# 10.net
KiCad netlist of a schematic drawn in Altium Designer
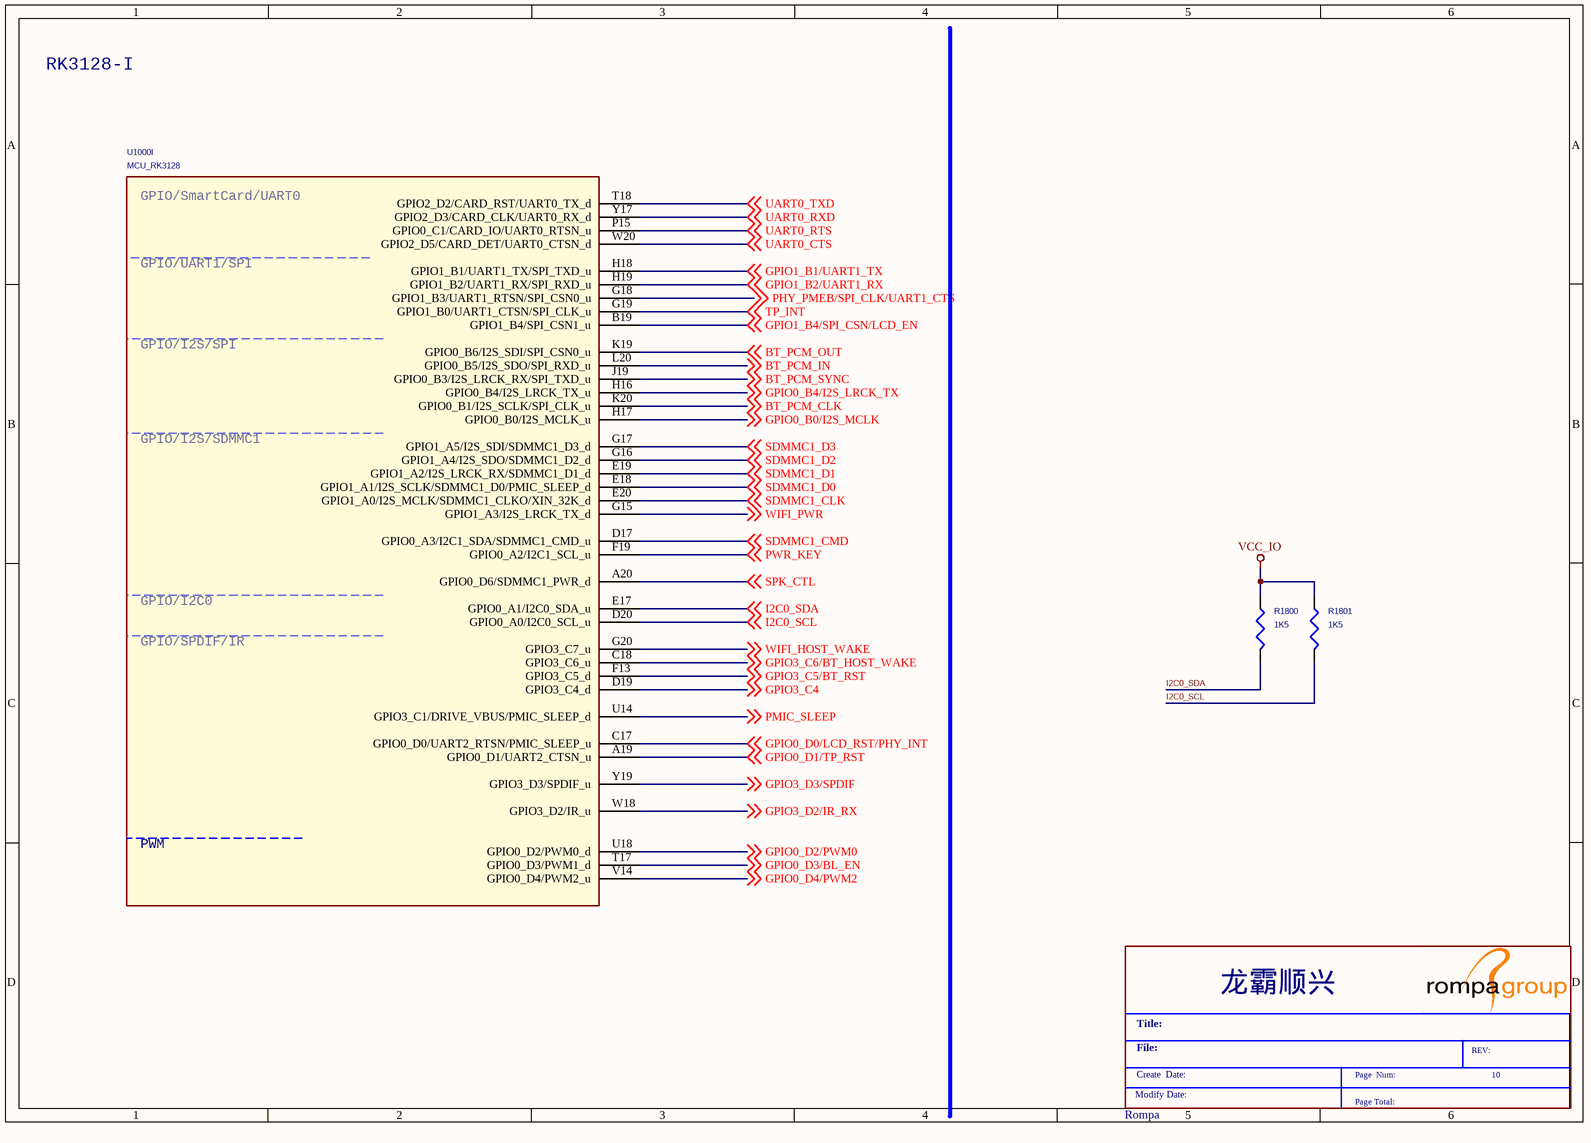
[diagram p0: 10.SchDoc]

(export (version "E")
  (design (tool "Eeschema 10.0.6"))
  (components
    (comp (ref "*")
      (value "Rompa")
      (fields (field (name "SCHEMATIC PAGE NUMBER") "10"))
      (libsource (lib "RK3128_BETA_V03_20151231_Library") (part "Rompa"))
    )
    (comp (ref "R1800")
      (value "1K5")
      (footprint "R0402")
      (description "ROHS CHIP RES 4.7K 1/16W 5%")
      (libsource (lib "*") (part "RES 1B"))
    )
    (comp (ref "R1801")
      (value "1K5")
      (footprint "R0402")
      (description "ROHS CHIP RES 4.7K 1/16W 5%")
      (libsource (lib "*") (part "RES 1B"))
    )
    (comp (ref "U1000")
      (value "MCU_RK3128")
      (footprint "BGA316-14X14-0.65")
      (libsource (lib "*") (part "MCU_RK3128"))
    )
  )
  (nets
    (net (code "1") (name "BT_PCM_CLK") (class "Default")
      (node (ref "U1000") (pin "K20") (pinfunction "GPIO0_B1/I2S_SCLK/SPI_CLK_u_K20") (pintype "passive"))
    )
    (net (code "2") (name "BT_PCM_IN") (class "Default")
      (node (ref "U1000") (pin "L20") (pinfunction "GPIO0_B5/I2S_SDO/SPI_RXD_u_L20") (pintype "passive"))
    )
    (net (code "3") (name "BT_PCM_OUT") (class "Default")
      (node (ref "U1000") (pin "K19") (pinfunction "GPIO0_B6/I2S_SDI/SPI_CSN0_u_K19") (pintype "passive"))
    )
    (net (code "4") (name "BT_PCM_SYNC") (class "Default")
      (node (ref "U1000") (pin "J19") (pinfunction "GPIO0_B3/I2S_LRCK_RX/SPI_TXD_u_J19") (pintype "passive"))
    )
    (net (code "5") (name "GPIO0_B0{slash}I2S_MCLK") (class "Default")
      (node (ref "U1000") (pin "H17") (pinfunction "GPIO0_B0/I2S_MCLK_u_H17") (pintype "passive"))
    )
    (net (code "6") (name "GPIO0_B4{slash}I2S_LRCK_TX") (class "Default")
      (node (ref "U1000") (pin "H16") (pinfunction "GPIO0_B4/I2S_LRCK_TX_u_H16") (pintype "passive"))
    )
    (net (code "7") (name "GPIO0_D0{slash}LCD_RST{slash}PHY_INT") (class "Default")
      (node (ref "U1000") (pin "C17") (pinfunction "GPIO0_D0/UART2_RTSN/PMIC_SLEEP_u_C17") (pintype "passive"))
    )
    (net (code "8") (name "GPIO0_D1{slash}TP_RST") (class "Default")
      (node (ref "U1000") (pin "A19") (pinfunction "GPIO0_D1/UART2_CTSN_u_A19") (pintype "passive"))
    )
    (net (code "9") (name "GPIO0_D2{slash}PWM0") (class "Default")
      (node (ref "U1000") (pin "U18") (pinfunction "GPIO0_D2/PWM0_d_U18") (pintype "passive"))
    )
    (net (code "10") (name "GPIO0_D3{slash}BL_EN") (class "Default")
      (node (ref "U1000") (pin "T17") (pinfunction "GPIO0_D3/PWM1_d_T17") (pintype "passive"))
    )
    (net (code "11") (name "GPIO0_D4{slash}PWM2") (class "Default")
      (node (ref "U1000") (pin "V14") (pinfunction "GPIO0_D4/PWM2_u_V14") (pintype "passive"))
    )
    (net (code "12") (name "GPIO1_B1{slash}UART1_TX") (class "Default")
      (node (ref "U1000") (pin "H18") (pinfunction "GPIO1_B1/UART1_TX/SPI_TXD_u_H18") (pintype "passive"))
    )
    (net (code "13") (name "GPIO1_B2{slash}UART1_RX") (class "Default")
      (node (ref "U1000") (pin "H19") (pinfunction "GPIO1_B2/UART1_RX/SPI_RXD_u_H19") (pintype "passive"))
    )
    (net (code "14") (name "GPIO1_B4{slash}SPI_CSN{slash}LCD_EN") (class "Default")
      (node (ref "U1000") (pin "B19") (pinfunction "GPIO1_B4/SPI_CSN1_u_B19") (pintype "passive"))
    )
    (net (code "15") (name "GPIO3_C4") (class "Default")
      (node (ref "U1000") (pin "D19") (pinfunction "GPIO3_C4_d_D19") (pintype "passive"))
    )
    (net (code "16") (name "GPIO3_C5{slash}BT_RST") (class "Default")
      (node (ref "U1000") (pin "F13") (pinfunction "GPIO3_C5_d_F13") (pintype "passive"))
    )
    (net (code "17") (name "GPIO3_C6{slash}BT_HOST_WAKE") (class "Default")
      (node (ref "U1000") (pin "C18") (pinfunction "GPIO3_C6_u_C18") (pintype "passive"))
    )
    (net (code "18") (name "GPIO3_D2{slash}IR_RX") (class "Default")
      (node (ref "U1000") (pin "W18") (pinfunction "GPIO3_D2/IR_u_W18") (pintype "passive"))
    )
    (net (code "19") (name "GPIO3_D3{slash}SPDIF") (class "Default")
      (node (ref "U1000") (pin "Y19") (pinfunction "GPIO3_D3/SPDIF_u_Y19") (pintype "passive"))
    )
    (net (code "20") (name "I2C0_SCL") (class "Default")
      (node (ref "R1801") (pin "2") (pinfunction "2_2") (pintype "passive"))
      (node (ref "U1000") (pin "D20") (pinfunction "GPIO0_A0/I2C0_SCL_u_D20") (pintype "passive"))
    )
    (net (code "21") (name "I2C0_SDA") (class "Default")
      (node (ref "R1800") (pin "2") (pinfunction "2_2") (pintype "passive"))
      (node (ref "U1000") (pin "E17") (pinfunction "GPIO0_A1/I2C0_SDA_u_E17") (pintype "passive"))
    )
    (net (code "22") (name "PHY_PMEB{slash}SPI_CLK{slash}UART1_CTS") (class "Default")
      (node (ref "U1000") (pin "G18") (pinfunction "GPIO1_B3/UART1_RTSN/SPI_CSN0_u_G18") (pintype "passive"))
    )
    (net (code "23") (name "PMIC_SLEEP") (class "Default")
      (node (ref "U1000") (pin "U14") (pinfunction "GPIO3_C1/DRIVE_VBUS/PMIC_SLEEP_d_U14") (pintype "passive"))
    )
    (net (code "24") (name "PWR_KEY") (class "Default")
      (node (ref "U1000") (pin "F19") (pinfunction "GPIO0_A2/I2C1_SCL_u_F19") (pintype "passive"))
    )
    (net (code "25") (name "SDMMC1_CLK") (class "Default")
      (node (ref "U1000") (pin "E20") (pinfunction "GPIO1_A0/I2S_MCLK/SDMMC1_CLKO/XIN_32K_d_E20") (pintype "passive"))
    )
    (net (code "26") (name "SDMMC1_CMD") (class "Default")
      (node (ref "U1000") (pin "D17") (pinfunction "GPIO0_A3/I2C1_SDA/SDMMC1_CMD_u_D17") (pintype "passive"))
    )
    (net (code "27") (name "SDMMC1_D0") (class "Default")
      (node (ref "U1000") (pin "E18") (pinfunction "GPIO1_A1/I2S_SCLK/SDMMC1_D0/PMIC_SLEEP_d_E18") (pintype "passive"))
    )
    (net (code "28") (name "SDMMC1_D1") (class "Default")
      (node (ref "U1000") (pin "E19") (pinfunction "GPIO1_A2/I2S_LRCK_RX/SDMMC1_D1_d_E19") (pintype "passive"))
    )
    (net (code "29") (name "SDMMC1_D2") (class "Default")
      (node (ref "U1000") (pin "G16") (pinfunction "GPIO1_A4/I2S_SDO/SDMMC1_D2_d_G16") (pintype "passive"))
    )
    (net (code "30") (name "SDMMC1_D3") (class "Default")
      (node (ref "U1000") (pin "G17") (pinfunction "GPIO1_A5/I2S_SDI/SDMMC1_D3_d_G17") (pintype "passive"))
    )
    (net (code "31") (name "SPK_CTL") (class "Default")
      (node (ref "U1000") (pin "A20") (pinfunction "GPIO0_D6/SDMMC1_PWR_d_A20") (pintype "passive"))
    )
    (net (code "32") (name "TP_INT") (class "Default")
      (node (ref "U1000") (pin "G19") (pinfunction "GPIO1_B0/UART1_CTSN/SPI_CLK_u_G19") (pintype "passive"))
    )
    (net (code "33") (name "UART0_CTS") (class "Default")
      (node (ref "U1000") (pin "W20") (pinfunction "GPIO2_D5/CARD_DET/UART0_CTSN_d_W20") (pintype "passive"))
    )
    (net (code "34") (name "UART0_RTS") (class "Default")
      (node (ref "U1000") (pin "P15") (pinfunction "GPIO0_C1/CARD_IO/UART0_RTSN_u_P15") (pintype "passive"))
    )
    (net (code "35") (name "UART0_RXD") (class "Default")
      (node (ref "U1000") (pin "Y17") (pinfunction "GPIO2_D3/CARD_CLK/UART0_RX_d_Y17") (pintype "passive"))
    )
    (net (code "36") (name "UART0_TXD") (class "Default")
      (node (ref "U1000") (pin "T18") (pinfunction "GPIO2_D2/CARD_RST/UART0_TX_d_T18") (pintype "passive"))
    )
    (net (code "37") (name "VCC_IO") (class "Default")
      (node (ref "R1800") (pin "1") (pinfunction "1_1") (pintype "passive"))
      (node (ref "R1801") (pin "1") (pinfunction "1_1") (pintype "passive"))
    )
    (net (code "38") (name "WIFI_HOST_WAKE") (class "Default")
      (node (ref "U1000") (pin "G20") (pinfunction "GPIO3_C7_u_G20") (pintype "passive"))
    )
    (net (code "39") (name "WIFI_PWR") (class "Default")
      (node (ref "U1000") (pin "G15") (pinfunction "GPIO1_A3/I2S_LRCK_TX_d_G15") (pintype "passive"))
    )
  )
)
